# board_IR.net
KiCad netlist of a schematic drawn in EAGLE
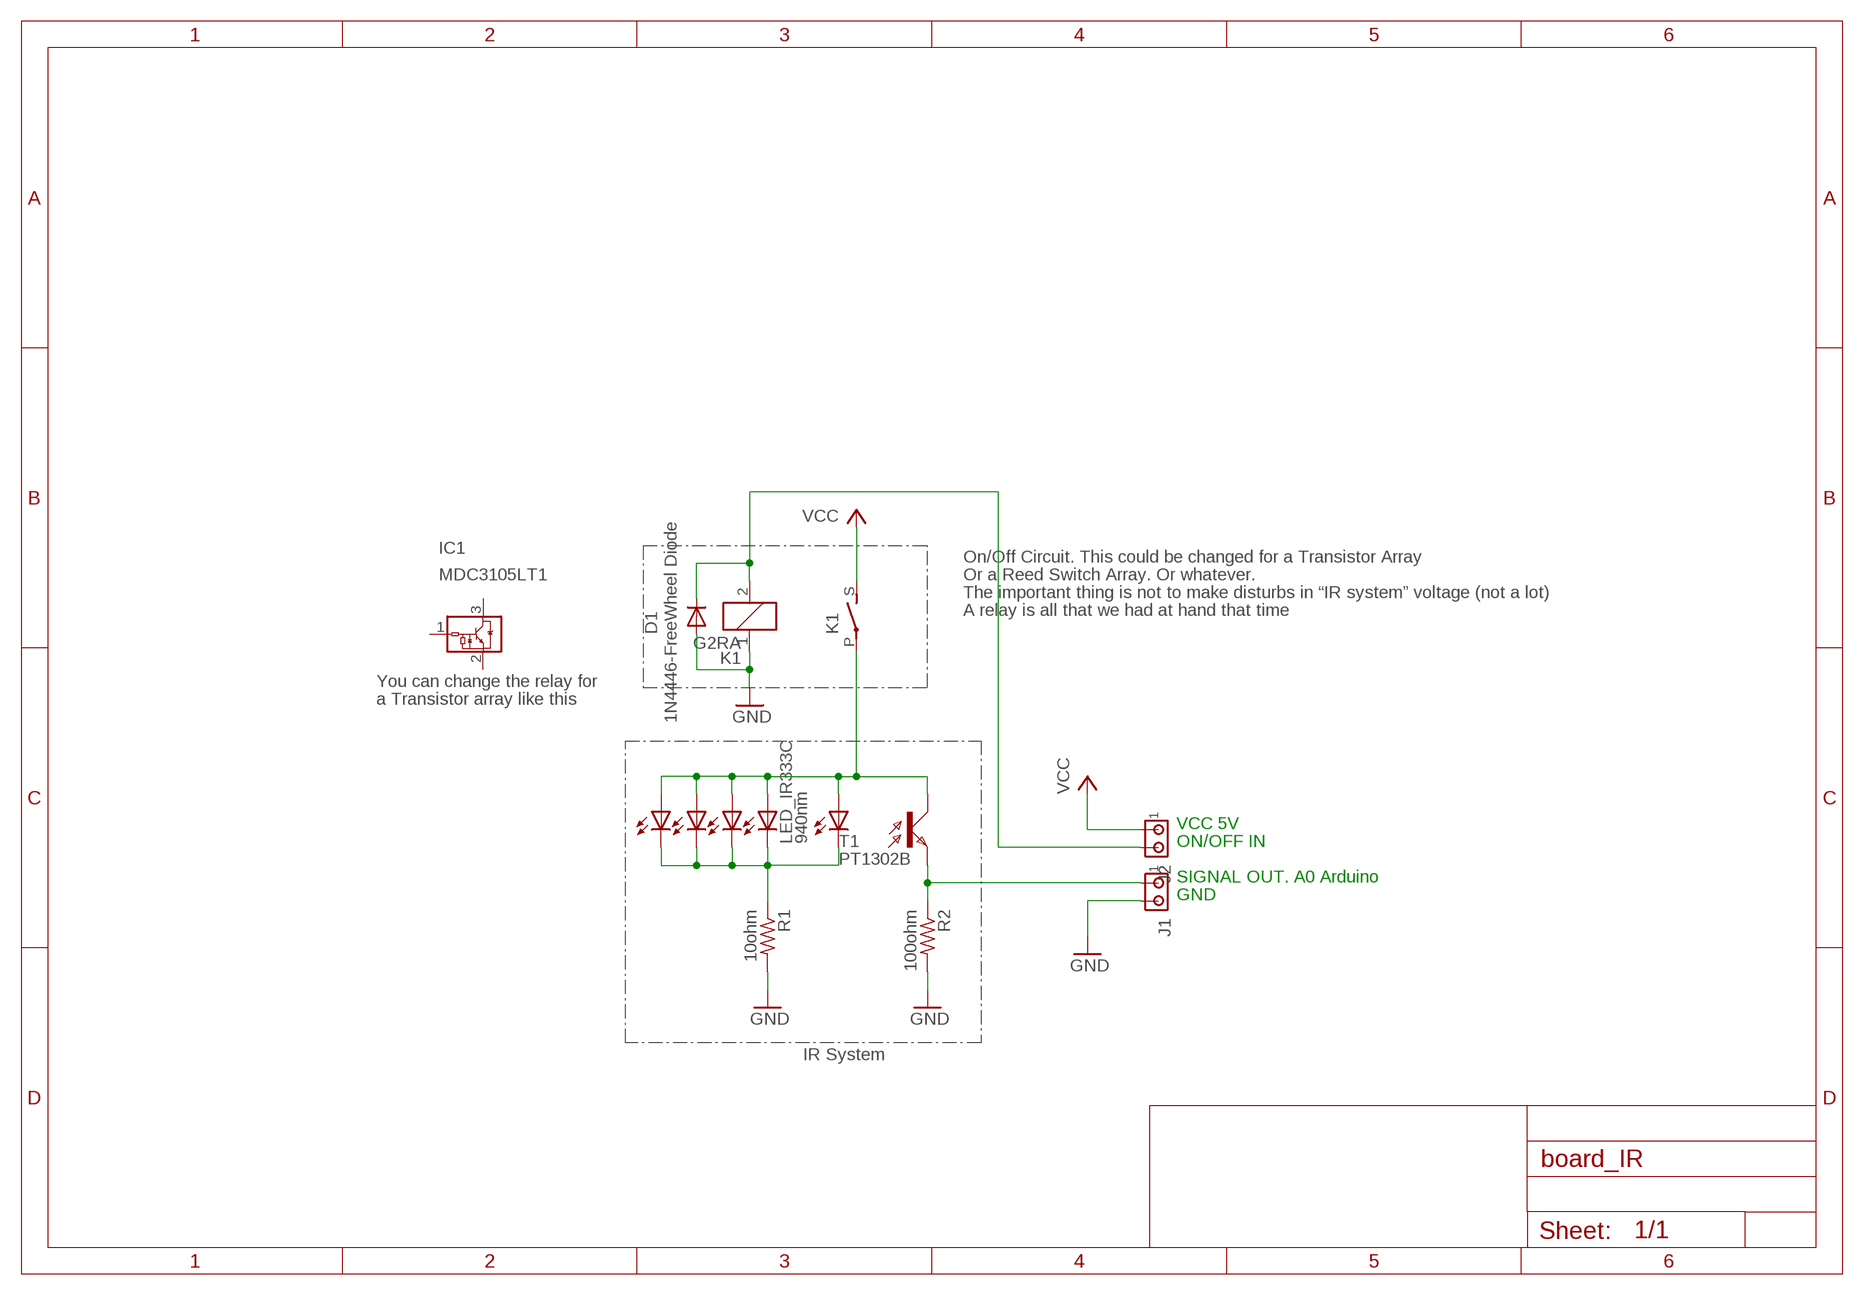
[diagram p0: schematic, sheet 1]

(export (version "E")
  (design (tool "Eeschema 10.0.6"))
  (components
    (comp (ref "D1")
      (value "1N4446-FreeWheel Diode")
      (footprint "eagle-import:DO35-10")
      (libsource (lib "eagle-import") (part "1N4446"))
    )
    (comp (ref "IC1")
      (value "MDC3105LT1")
      (footprint "eagle-import:SOT23")
      (fields (field (name "MF") "ON SEMICONDUCTOR"))
      (libsource (lib "eagle-import") (part "MDC3105LT1"))
    )
    (comp (ref "J1")
      (value "MTA02-156")
      (footprint "eagle-import:1X2MTA")
      (libsource (lib "eagle-import") (part "MTA02-156"))
    )
    (comp (ref "J2")
      (value "MTA02-156")
      (footprint "eagle-import:1X2MTA")
      (libsource (lib "eagle-import") (part "MTA02-156"))
    )
    (comp (ref "K1")
      (value "G2RA")
      (footprint "eagle-import:G2RA")
      (libsource (lib "eagle-import") (part "G2RA"))
    )
    (comp (ref "LED_IR333C")
      (value "940nm")
      (footprint "eagle-import:LED5MM")
      (libsource (lib "eagle-import") (part "LED5MM"))
    )
    (comp (ref "LED_IR333C1")
      (value "940nm")
      (footprint "eagle-import:LED5MM")
      (libsource (lib "eagle-import") (part "LED5MM"))
    )
    (comp (ref "LED_IR333C2")
      (value "940nm")
      (footprint "eagle-import:LED5MM")
      (libsource (lib "eagle-import") (part "LED5MM"))
    )
    (comp (ref "LED_IR333C3")
      (value "940nm")
      (footprint "eagle-import:LED5MM")
      (libsource (lib "eagle-import") (part "LED5MM"))
    )
    (comp (ref "LED_IR333C4")
      (value "940nm")
      (footprint "eagle-import:LED5MM")
      (libsource (lib "eagle-import") (part "LED5MM"))
    )
    (comp (ref "R1")
      (value "10ohm")
      (footprint "eagle-import:0204_7")
      (libsource (lib "eagle-import") (part "R-US_0204/7"))
    )
    (comp (ref "R2")
      (value "100ohm")
      (footprint "eagle-import:0204_7")
      (libsource (lib "eagle-import") (part "R-US_0204/7"))
    )
    (comp (ref "T1")
      (value "PT1302B")
      (footprint "eagle-import:LPT80A")
      (libsource (lib "eagle-import") (part "LPT80A"))
    )
  )
  (nets
    (net (code "1") (name "GND") (class "Default")
      (node (ref "D1") (pin "A") (pinfunction "A_A") (pintype "passive"))
      (node (ref "J1") (pin "2") (pinfunction "2_2") (pintype "passive"))
      (node (ref "K1") (pin "1") (pinfunction "1_1") (pintype "passive"))
      (node (ref "R1") (pin "2") (pinfunction "2_2") (pintype "passive"))
      (node (ref "R2") (pin "2") (pinfunction "2_2") (pintype "passive"))
    )
    (net (code "2") (name "Net-(D1-PadC)") (class "Default")
      (node (ref "D1") (pin "C") (pinfunction "C_C") (pintype "passive"))
      (node (ref "J2") (pin "2") (pinfunction "2_2") (pintype "passive"))
      (node (ref "K1") (pin "2") (pinfunction "2_2") (pintype "passive"))
    )
    (net (code "3") (name "Net-(J1-Pad1)") (class "Default")
      (node (ref "J1") (pin "1") (pinfunction "1_1") (pintype "passive"))
      (node (ref "R2") (pin "1") (pinfunction "1_1") (pintype "passive"))
      (node (ref "T1") (pin "E") (pinfunction "E_E") (pintype "passive"))
    )
    (net (code "4") (name "Net-(K1-PadP)") (class "Default")
      (node (ref "K1") (pin "P") (pinfunction "P_P") (pintype "passive"))
      (node (ref "LED_IR333C") (pin "A") (pinfunction "A_A") (pintype "passive"))
      (node (ref "LED_IR333C1") (pin "A") (pinfunction "A_A") (pintype "passive"))
      (node (ref "LED_IR333C2") (pin "A") (pinfunction "A_A") (pintype "passive"))
      (node (ref "LED_IR333C3") (pin "A") (pinfunction "A_A") (pintype "passive"))
      (node (ref "LED_IR333C4") (pin "A") (pinfunction "A_A") (pintype "passive"))
      (node (ref "T1") (pin "C") (pinfunction "C_C") (pintype "passive"))
    )
    (net (code "5") (name "Net-(LED_IR333C-C)") (class "Default")
      (node (ref "LED_IR333C") (pin "K") (pinfunction "C_K") (pintype "passive"))
      (node (ref "LED_IR333C1") (pin "K") (pinfunction "C_K") (pintype "passive"))
      (node (ref "LED_IR333C2") (pin "K") (pinfunction "C_K") (pintype "passive"))
      (node (ref "LED_IR333C3") (pin "K") (pinfunction "C_K") (pintype "passive"))
      (node (ref "LED_IR333C4") (pin "K") (pinfunction "C_K") (pintype "passive"))
      (node (ref "R1") (pin "1") (pinfunction "1_1") (pintype "passive"))
    )
    (net (code "6") (name "VCC") (class "Default")
      (node (ref "J2") (pin "1") (pinfunction "1_1") (pintype "passive"))
      (node (ref "K1") (pin "S") (pinfunction "S_S") (pintype "passive"))
    )
    (net (code "7") (name "unconnected-(IC1-GND-Pad2)") (class "Default")
      (node (ref "IC1") (pin "2") (pinfunction "GND_2") (pintype "passive"))
    )
    (net (code "8") (name "unconnected-(IC1-VIN-Pad1)") (class "Default")
      (node (ref "IC1") (pin "1") (pinfunction "VIN_1") (pintype "passive"))
    )
    (net (code "9") (name "unconnected-(IC1-VOUT-Pad3)") (class "Default")
      (node (ref "IC1") (pin "3") (pinfunction "VOUT_3") (pintype "passive"))
    )
  )
)
